# untitled.net
KiCad netlist of a schematic drawn in EAGLE
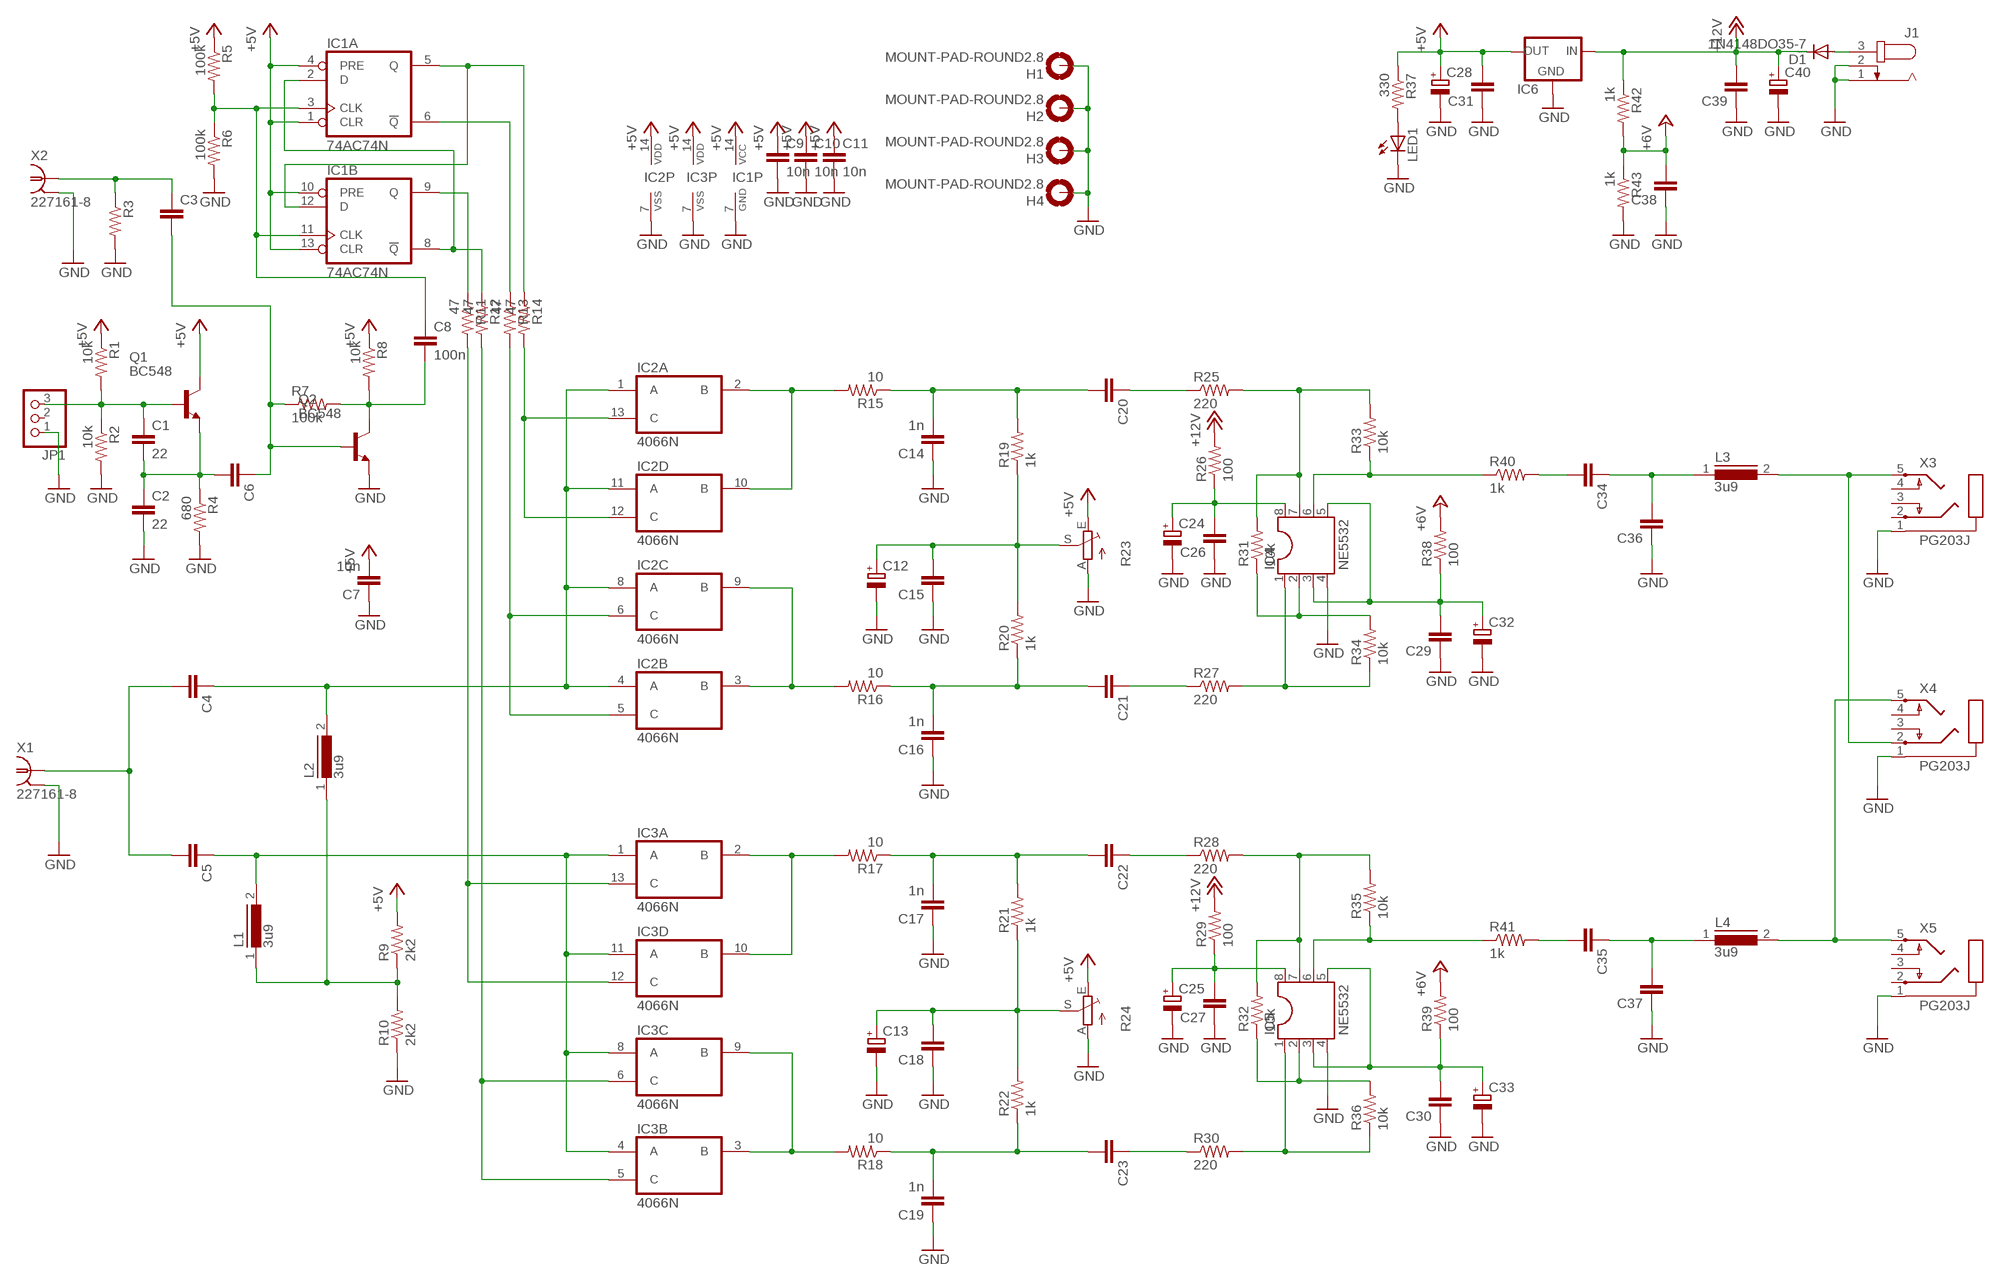
[diagram p0: schematic, sheet 1]

(export (version "E")
  (design (tool "Eeschema 10.0.6"))
  (components
    (comp (ref "C1")
      (value "22")
      (footprint "eagle-import:C025-025X050")
      (libsource (lib "eagle-import") (part "C-EU025-025X050"))
    )
    (comp (ref "C2")
      (value "22")
      (footprint "eagle-import:C025-025X050")
      (libsource (lib "eagle-import") (part "C-EU025-025X050"))
    )
    (comp (ref "C3")
      (value "C-EU050-025X075")
      (footprint "eagle-import:C050-025X075")
      (libsource (lib "eagle-import") (part "C-EU050-025X075"))
    )
    (comp (ref "C4")
      (value "C-EU050-025X075")
      (footprint "eagle-import:C050-025X075")
      (libsource (lib "eagle-import") (part "C-EU050-025X075"))
    )
    (comp (ref "C5")
      (value "C-EU050-025X075")
      (footprint "eagle-import:C050-025X075")
      (libsource (lib "eagle-import") (part "C-EU050-025X075"))
    )
    (comp (ref "C6")
      (value "C-EU050-025X075")
      (footprint "eagle-import:C050-025X075")
      (libsource (lib "eagle-import") (part "C-EU050-025X075"))
    )
    (comp (ref "C7")
      (value "10n")
      (footprint "eagle-import:C050-025X075")
      (libsource (lib "eagle-import") (part "C-EU050-025X075"))
    )
    (comp (ref "C8")
      (value "100n")
      (footprint "eagle-import:C075-032X103")
      (libsource (lib "eagle-import") (part "C-EU075-032X103"))
    )
    (comp (ref "C9")
      (value "10n")
      (footprint "eagle-import:C050-025X075")
      (libsource (lib "eagle-import") (part "C-EU050-025X075"))
    )
    (comp (ref "C10")
      (value "10n")
      (footprint "eagle-import:C050-025X075")
      (libsource (lib "eagle-import") (part "C-EU050-025X075"))
    )
    (comp (ref "C11")
      (value "10n")
      (footprint "eagle-import:C050-025X075")
      (libsource (lib "eagle-import") (part "C-EU050-025X075"))
    )
    (comp (ref "C12")
      (value "CPOL-EUE5-6")
      (footprint "eagle-import:E5-6")
      (libsource (lib "eagle-import") (part "CPOL-EUE5-6"))
    )
    (comp (ref "C13")
      (value "CPOL-EUE5-6")
      (footprint "eagle-import:E5-6")
      (libsource (lib "eagle-import") (part "CPOL-EUE5-6"))
    )
    (comp (ref "C14")
      (value "1n")
      (footprint "eagle-import:C050-025X075")
      (libsource (lib "eagle-import") (part "C-EU050-025X075"))
    )
    (comp (ref "C15")
      (value "C-EU050-025X075")
      (footprint "eagle-import:C050-025X075")
      (libsource (lib "eagle-import") (part "C-EU050-025X075"))
    )
    (comp (ref "C16")
      (value "1n")
      (footprint "eagle-import:C050-025X075")
      (libsource (lib "eagle-import") (part "C-EU050-025X075"))
    )
    (comp (ref "C17")
      (value "1n")
      (footprint "eagle-import:C050-025X075")
      (libsource (lib "eagle-import") (part "C-EU050-025X075"))
    )
    (comp (ref "C18")
      (value "C-EU050-025X075")
      (footprint "eagle-import:C050-025X075")
      (libsource (lib "eagle-import") (part "C-EU050-025X075"))
    )
    (comp (ref "C19")
      (value "1n")
      (footprint "eagle-import:C050-025X075")
      (libsource (lib "eagle-import") (part "C-EU050-025X075"))
    )
    (comp (ref "C20")
      (value "C-EU050-025X075")
      (footprint "eagle-import:C050-025X075")
      (libsource (lib "eagle-import") (part "C-EU050-025X075"))
    )
    (comp (ref "C21")
      (value "C-EU050-025X075")
      (footprint "eagle-import:C050-025X075")
      (libsource (lib "eagle-import") (part "C-EU050-025X075"))
    )
    (comp (ref "C22")
      (value "C-EU050-025X075")
      (footprint "eagle-import:C050-025X075")
      (libsource (lib "eagle-import") (part "C-EU050-025X075"))
    )
    (comp (ref "C23")
      (value "C-EU050-025X075")
      (footprint "eagle-import:C050-025X075")
      (libsource (lib "eagle-import") (part "C-EU050-025X075"))
    )
    (comp (ref "C24")
      (value "CPOL-EUE5-6")
      (footprint "eagle-import:E5-6")
      (libsource (lib "eagle-import") (part "CPOL-EUE5-6"))
    )
    (comp (ref "C25")
      (value "CPOL-EUE5-6")
      (footprint "eagle-import:E5-6")
      (libsource (lib "eagle-import") (part "CPOL-EUE5-6"))
    )
    (comp (ref "C26")
      (value "C-EU050-025X075")
      (footprint "eagle-import:C050-025X075")
      (libsource (lib "eagle-import") (part "C-EU050-025X075"))
    )
    (comp (ref "C27")
      (value "C-EU050-025X075")
      (footprint "eagle-import:C050-025X075")
      (libsource (lib "eagle-import") (part "C-EU050-025X075"))
    )
    (comp (ref "C28")
      (value "CPOL-EUE5-6")
      (footprint "eagle-import:E5-6")
      (libsource (lib "eagle-import") (part "CPOL-EUE5-6"))
    )
    (comp (ref "C29")
      (value "C-EU050-025X075")
      (footprint "eagle-import:C050-025X075")
      (libsource (lib "eagle-import") (part "C-EU050-025X075"))
    )
    (comp (ref "C30")
      (value "C-EU050-025X075")
      (footprint "eagle-import:C050-025X075")
      (libsource (lib "eagle-import") (part "C-EU050-025X075"))
    )
    (comp (ref "C31")
      (value "C-EU050-025X075")
      (footprint "eagle-import:C050-025X075")
      (libsource (lib "eagle-import") (part "C-EU050-025X075"))
    )
    (comp (ref "C32")
      (value "CPOL-EUE5-6")
      (footprint "eagle-import:E5-6")
      (libsource (lib "eagle-import") (part "CPOL-EUE5-6"))
    )
    (comp (ref "C33")
      (value "CPOL-EUE5-6")
      (footprint "eagle-import:E5-6")
      (libsource (lib "eagle-import") (part "CPOL-EUE5-6"))
    )
    (comp (ref "C34")
      (value "C-EU050-025X075")
      (footprint "eagle-import:C050-025X075")
      (libsource (lib "eagle-import") (part "C-EU050-025X075"))
    )
    (comp (ref "C35")
      (value "C-EU050-025X075")
      (footprint "eagle-import:C050-025X075")
      (libsource (lib "eagle-import") (part "C-EU050-025X075"))
    )
    (comp (ref "C36")
      (value "C-EU050-025X075")
      (footprint "eagle-import:C050-025X075")
      (libsource (lib "eagle-import") (part "C-EU050-025X075"))
    )
    (comp (ref "C37")
      (value "C-EU050-025X075")
      (footprint "eagle-import:C050-025X075")
      (libsource (lib "eagle-import") (part "C-EU050-025X075"))
    )
    (comp (ref "C38")
      (value "C-EU050-025X075")
      (footprint "eagle-import:C050-025X075")
      (libsource (lib "eagle-import") (part "C-EU050-025X075"))
    )
    (comp (ref "C39")
      (value "C-EU050-025X075")
      (footprint "eagle-import:C050-025X075")
      (libsource (lib "eagle-import") (part "C-EU050-025X075"))
    )
    (comp (ref "C40")
      (value "CPOL-EUE5-6")
      (footprint "eagle-import:E5-6")
      (libsource (lib "eagle-import") (part "CPOL-EUE5-6"))
    )
    (comp (ref "D1")
      (value "1N4148DO35-7")
      (footprint "eagle-import:DO35-7")
      (libsource (lib "eagle-import") (part "1N4148DO35-7"))
    )
    (comp (ref "H1")
      (value "MOUNT-PAD-ROUND2.8")
      (footprint "eagle-import:2,8-PAD")
      (libsource (lib "eagle-import") (part "MOUNT-PAD-ROUND2.8"))
    )
    (comp (ref "H2")
      (value "MOUNT-PAD-ROUND2.8")
      (footprint "eagle-import:2,8-PAD")
      (libsource (lib "eagle-import") (part "MOUNT-PAD-ROUND2.8"))
    )
    (comp (ref "H3")
      (value "MOUNT-PAD-ROUND2.8")
      (footprint "eagle-import:2,8-PAD")
      (libsource (lib "eagle-import") (part "MOUNT-PAD-ROUND2.8"))
    )
    (comp (ref "H4")
      (value "MOUNT-PAD-ROUND2.8")
      (footprint "eagle-import:2,8-PAD")
      (libsource (lib "eagle-import") (part "MOUNT-PAD-ROUND2.8"))
    )
    (comp (ref "IC1")
      (value "74AC74N")
      (footprint "eagle-import:DIL14")
      (libsource (lib "eagle-import") (part "7474NAC"))
    )
    (comp (ref "IC2")
      (value "4066N")
      (footprint "eagle-import:DIL14")
      (libsource (lib "eagle-import") (part "4066N"))
    )
    (comp (ref "IC3")
      (value "4066N")
      (footprint "eagle-import:DIL14")
      (libsource (lib "eagle-import") (part "4066N"))
    )
    (comp (ref "IC4")
      (value "NE5532")
      (footprint "eagle-import:DIL08")
      (libsource (lib "eagle-import") (part "DIL8"))
    )
    (comp (ref "IC5")
      (value "NE5532")
      (footprint "eagle-import:DIL08")
      (libsource (lib "eagle-import") (part "DIL8"))
    )
    (comp (ref "IC6")
      (value "78XXS")
      (footprint "eagle-import:78XXS")
      (libsource (lib "eagle-import") (part "78XXS"))
    )
    (comp (ref "J1")
      (value "JACK-PLUG0")
      (footprint "eagle-import:SPC4077")
      (libsource (lib "eagle-import") (part "JACK-PLUG0"))
    )
    (comp (ref "JP1")
      (value "PINHD-1X3")
      (footprint "eagle-import:1X03")
      (libsource (lib "eagle-import") (part "PINHD-1X3"))
    )
    (comp (ref "L1")
      (value "3u9")
      (footprint "eagle-import:MMICC7")
      (libsource (lib "eagle-import") (part "MMICC7"))
    )
    (comp (ref "L2")
      (value "3u9")
      (footprint "eagle-import:MMICC7")
      (libsource (lib "eagle-import") (part "MMICC7"))
    )
    (comp (ref "L3")
      (value "3u9")
      (footprint "eagle-import:MMICC7")
      (libsource (lib "eagle-import") (part "MMICC7"))
    )
    (comp (ref "L4")
      (value "3u9")
      (footprint "eagle-import:MMICC7")
      (libsource (lib "eagle-import") (part "MMICC7"))
    )
    (comp (ref "LED1")
      (value "LED3MM")
      (footprint "eagle-import:LED3MM")
      (libsource (lib "eagle-import") (part "LED3MM"))
    )
    (comp (ref "Q1")
      (value "BC548")
      (footprint "eagle-import:TO92-EBC")
      (libsource (lib "eagle-import") (part "BC548"))
    )
    (comp (ref "Q2")
      (value "BC548")
      (footprint "eagle-import:TO92-EBC")
      (libsource (lib "eagle-import") (part "BC548"))
    )
    (comp (ref "R1")
      (value "10k")
      (footprint "eagle-import:0207_7")
      (libsource (lib "eagle-import") (part "R-US_0207/7"))
    )
    (comp (ref "R2")
      (value "10k")
      (footprint "eagle-import:0207_7")
      (libsource (lib "eagle-import") (part "R-US_0207/7"))
    )
    (comp (ref "R3")
      (value "R-US_0207/7")
      (footprint "eagle-import:0207_7")
      (libsource (lib "eagle-import") (part "R-US_0207/7"))
    )
    (comp (ref "R4")
      (value "680")
      (footprint "eagle-import:0207_7")
      (libsource (lib "eagle-import") (part "R-US_0207/7"))
    )
    (comp (ref "R5")
      (value "100k")
      (footprint "eagle-import:0207_7")
      (libsource (lib "eagle-import") (part "R-US_0207/7"))
    )
    (comp (ref "R6")
      (value "100k")
      (footprint "eagle-import:0207_7")
      (libsource (lib "eagle-import") (part "R-US_0207/7"))
    )
    (comp (ref "R7")
      (value "100k")
      (footprint "eagle-import:0207_7")
      (libsource (lib "eagle-import") (part "R-US_0207/7"))
    )
    (comp (ref "R8")
      (value "10k")
      (footprint "eagle-import:0207_7")
      (libsource (lib "eagle-import") (part "R-US_0207/7"))
    )
    (comp (ref "R9")
      (value "2k2")
      (footprint "eagle-import:0207_7")
      (libsource (lib "eagle-import") (part "R-US_0207/7"))
    )
    (comp (ref "R10")
      (value "2k2")
      (footprint "eagle-import:0207_7")
      (libsource (lib "eagle-import") (part "R-US_0207/7"))
    )
    (comp (ref "R11")
      (value "47")
      (footprint "eagle-import:0207_7")
      (libsource (lib "eagle-import") (part "R-US_0207/7"))
    )
    (comp (ref "R12")
      (value "47")
      (footprint "eagle-import:0207_7")
      (libsource (lib "eagle-import") (part "R-US_0207/7"))
    )
    (comp (ref "R13")
      (value "47")
      (footprint "eagle-import:0207_7")
      (libsource (lib "eagle-import") (part "R-US_0207/7"))
    )
    (comp (ref "R14")
      (value "47")
      (footprint "eagle-import:0207_7")
      (libsource (lib "eagle-import") (part "R-US_0207/7"))
    )
    (comp (ref "R15")
      (value "10")
      (footprint "eagle-import:0207_7")
      (libsource (lib "eagle-import") (part "R-US_0207/7"))
    )
    (comp (ref "R16")
      (value "10")
      (footprint "eagle-import:0207_7")
      (libsource (lib "eagle-import") (part "R-US_0207/7"))
    )
    (comp (ref "R17")
      (value "10")
      (footprint "eagle-import:0207_7")
      (libsource (lib "eagle-import") (part "R-US_0207/7"))
    )
    (comp (ref "R18")
      (value "10")
      (footprint "eagle-import:0207_7")
      (libsource (lib "eagle-import") (part "R-US_0207/7"))
    )
    (comp (ref "R19")
      (value "1k")
      (footprint "eagle-import:0207_7")
      (libsource (lib "eagle-import") (part "R-US_0207/7"))
    )
    (comp (ref "R20")
      (value "1k")
      (footprint "eagle-import:0207_7")
      (libsource (lib "eagle-import") (part "R-US_0207/7"))
    )
    (comp (ref "R21")
      (value "1k")
      (footprint "eagle-import:0207_7")
      (libsource (lib "eagle-import") (part "R-US_0207/7"))
    )
    (comp (ref "R22")
      (value "1k")
      (footprint "eagle-import:0207_7")
      (libsource (lib "eagle-import") (part "R-US_0207/7"))
    )
    (comp (ref "R23")
      (value "TRIM_EU-B64Y")
      (footprint "eagle-import:B64Y")
      (libsource (lib "eagle-import") (part "TRIM_EU-B64Y"))
    )
    (comp (ref "R24")
      (value "TRIM_EU-B64Y")
      (footprint "eagle-import:B64Y")
      (libsource (lib "eagle-import") (part "TRIM_EU-B64Y"))
    )
    (comp (ref "R25")
      (value "220")
      (footprint "eagle-import:0207_7")
      (libsource (lib "eagle-import") (part "R-US_0207/7"))
    )
    (comp (ref "R26")
      (value "100")
      (footprint "eagle-import:0207_7")
      (libsource (lib "eagle-import") (part "R-US_0207/7"))
    )
    (comp (ref "R27")
      (value "220")
      (footprint "eagle-import:0207_7")
      (libsource (lib "eagle-import") (part "R-US_0207/7"))
    )
    (comp (ref "R28")
      (value "220")
      (footprint "eagle-import:0207_7")
      (libsource (lib "eagle-import") (part "R-US_0207/7"))
    )
    (comp (ref "R29")
      (value "100")
      (footprint "eagle-import:0207_7")
      (libsource (lib "eagle-import") (part "R-US_0207/7"))
    )
    (comp (ref "R30")
      (value "220")
      (footprint "eagle-import:0207_7")
      (libsource (lib "eagle-import") (part "R-US_0207/7"))
    )
    (comp (ref "R31")
      (value "10k")
      (footprint "eagle-import:0207_7")
      (libsource (lib "eagle-import") (part "R-US_0207/7"))
    )
    (comp (ref "R32")
      (value "10k")
      (footprint "eagle-import:0207_7")
      (libsource (lib "eagle-import") (part "R-US_0207/7"))
    )
    (comp (ref "R33")
      (value "10k")
      (footprint "eagle-import:0207_7")
      (libsource (lib "eagle-import") (part "R-US_0207/7"))
    )
    (comp (ref "R34")
      (value "10k")
      (footprint "eagle-import:0207_7")
      (libsource (lib "eagle-import") (part "R-US_0207/7"))
    )
    (comp (ref "R35")
      (value "10k")
      (footprint "eagle-import:0207_7")
      (libsource (lib "eagle-import") (part "R-US_0207/7"))
    )
    (comp (ref "R36")
      (value "10k")
      (footprint "eagle-import:0207_7")
      (libsource (lib "eagle-import") (part "R-US_0207/7"))
    )
    (comp (ref "R37")
      (value "330")
      (footprint "eagle-import:0207_7")
      (libsource (lib "eagle-import") (part "R-US_0207/7"))
    )
    (comp (ref "R38")
      (value "100")
      (footprint "eagle-import:0207_7")
      (libsource (lib "eagle-import") (part "R-US_0207/7"))
    )
    (comp (ref "R39")
      (value "100")
      (footprint "eagle-import:0207_7")
      (libsource (lib "eagle-import") (part "R-US_0207/7"))
    )
    (comp (ref "R40")
      (value "1k")
      (footprint "eagle-import:0207_7")
      (libsource (lib "eagle-import") (part "R-US_0207/7"))
    )
    (comp (ref "R41")
      (value "1k")
      (footprint "eagle-import:0207_7")
      (libsource (lib "eagle-import") (part "R-US_0207/7"))
    )
    (comp (ref "R42")
      (value "1k")
      (footprint "eagle-import:0207_7")
      (libsource (lib "eagle-import") (part "R-US_0207/7"))
    )
    (comp (ref "R43")
      (value "1k")
      (footprint "eagle-import:0207_7")
      (libsource (lib "eagle-import") (part "R-US_0207/7"))
    )
    (comp (ref "X1")
      (value "227161-8")
      (footprint "eagle-import:AMP_227161")
      (libsource (lib "eagle-import") (part "?227161-8"))
    )
    (comp (ref "X2")
      (value "227161-8")
      (footprint "eagle-import:AMP_227161")
      (libsource (lib "eagle-import") (part "?227161-8"))
    )
    (comp (ref "X3")
      (value "PG203J")
      (footprint "eagle-import:PG203J")
      (libsource (lib "eagle-import") (part "PG203J"))
    )
    (comp (ref "X4")
      (value "PG203J")
      (footprint "eagle-import:PG203J")
      (libsource (lib "eagle-import") (part "PG203J"))
    )
    (comp (ref "X5")
      (value "PG203J")
      (footprint "eagle-import:PG203J")
      (libsource (lib "eagle-import") (part "PG203J"))
    )
  )
  (nets
    (net (code "1") (name "+5V") (class "Default")
      (node (ref "C10") (pin "1") (pinfunction "1_1") (pintype "passive"))
      (node (ref "C11") (pin "1") (pinfunction "1_1") (pintype "passive"))
      (node (ref "C28") (pin "+") (pinfunction "+_+") (pintype "passive"))
      (node (ref "C31") (pin "2") (pinfunction "2_2") (pintype "passive"))
      (node (ref "C7") (pin "2") (pinfunction "2_2") (pintype "passive"))
      (node (ref "C9") (pin "1") (pinfunction "1_1") (pintype "passive"))
      (node (ref "IC1") (pin "1") (pinfunction "CLR_1") (pintype "input"))
      (node (ref "IC1") (pin "10") (pinfunction "PRE_10") (pintype "input"))
      (node (ref "IC1") (pin "13") (pinfunction "CLR_13") (pintype "input"))
      (node (ref "IC1") (pin "14") (pinfunction "VCC_14") (pintype "power_in"))
      (node (ref "IC1") (pin "4") (pinfunction "PRE_4") (pintype "input"))
      (node (ref "IC2") (pin "14") (pinfunction "VDD_14") (pintype "power_in"))
      (node (ref "IC3") (pin "14") (pinfunction "VDD_14") (pintype "power_in"))
      (node (ref "IC6") (pin "OUT") (pinfunction "OUT_OUT") (pintype "passive"))
      (node (ref "Q1") (pin "C") (pinfunction "C_C") (pintype "passive"))
      (node (ref "R1") (pin "1") (pinfunction "1_1") (pintype "passive"))
      (node (ref "R23") (pin "E") (pinfunction "E_E") (pintype "passive"))
      (node (ref "R24") (pin "E") (pinfunction "E_E") (pintype "passive"))
      (node (ref "R37") (pin "1") (pinfunction "1_1") (pintype "passive"))
      (node (ref "R5") (pin "1") (pinfunction "1_1") (pintype "passive"))
      (node (ref "R8") (pin "1") (pinfunction "1_1") (pintype "passive"))
      (node (ref "R9") (pin "2") (pinfunction "2_2") (pintype "passive"))
    )
    (net (code "2") (name "+6V") (class "Default")
      (node (ref "C38") (pin "2") (pinfunction "2_2") (pintype "passive"))
      (node (ref "R38") (pin "2") (pinfunction "2_2") (pintype "passive"))
      (node (ref "R39") (pin "2") (pinfunction "2_2") (pintype "passive"))
      (node (ref "R42") (pin "2") (pinfunction "2_2") (pintype "passive"))
      (node (ref "R43") (pin "1") (pinfunction "1_1") (pintype "passive"))
    )
    (net (code "3") (name "+12V") (class "Default")
      (node (ref "C39") (pin "2") (pinfunction "2_2") (pintype "passive"))
      (node (ref "C40") (pin "+") (pinfunction "+_+") (pintype "passive"))
      (node (ref "D1") (pin "C") (pinfunction "C_C") (pintype "passive"))
      (node (ref "IC6") (pin "IN") (pinfunction "IN_IN") (pintype "input"))
      (node (ref "R26") (pin "2") (pinfunction "2_2") (pintype "passive"))
      (node (ref "R29") (pin "2") (pinfunction "2_2") (pintype "passive"))
      (node (ref "R42") (pin "1") (pinfunction "1_1") (pintype "passive"))
    )
    (net (code "4") (name "GND") (class "Default")
      (node (ref "C10") (pin "2") (pinfunction "2_2") (pintype "passive"))
      (node (ref "C11") (pin "2") (pinfunction "2_2") (pintype "passive"))
      (node (ref "C12") (pin "-") (pinfunction "-_-") (pintype "passive"))
      (node (ref "C13") (pin "-") (pinfunction "-_-") (pintype "passive"))
      (node (ref "C14") (pin "1") (pinfunction "1_1") (pintype "passive"))
      (node (ref "C15") (pin "1") (pinfunction "1_1") (pintype "passive"))
      (node (ref "C16") (pin "1") (pinfunction "1_1") (pintype "passive"))
      (node (ref "C17") (pin "1") (pinfunction "1_1") (pintype "passive"))
      (node (ref "C18") (pin "1") (pinfunction "1_1") (pintype "passive"))
      (node (ref "C19") (pin "1") (pinfunction "1_1") (pintype "passive"))
      (node (ref "C2") (pin "2") (pinfunction "2_2") (pintype "passive"))
      (node (ref "C24") (pin "-") (pinfunction "-_-") (pintype "passive"))
      (node (ref "C25") (pin "-") (pinfunction "-_-") (pintype "passive"))
      (node (ref "C26") (pin "1") (pinfunction "1_1") (pintype "passive"))
      (node (ref "C27") (pin "1") (pinfunction "1_1") (pintype "passive"))
      (node (ref "C28") (pin "-") (pinfunction "-_-") (pintype "passive"))
      (node (ref "C29") (pin "1") (pinfunction "1_1") (pintype "passive"))
      (node (ref "C30") (pin "1") (pinfunction "1_1") (pintype "passive"))
      (node (ref "C31") (pin "1") (pinfunction "1_1") (pintype "passive"))
      (node (ref "C32") (pin "-") (pinfunction "-_-") (pintype "passive"))
      (node (ref "C33") (pin "-") (pinfunction "-_-") (pintype "passive"))
      (node (ref "C36") (pin "1") (pinfunction "1_1") (pintype "passive"))
      (node (ref "C37") (pin "1") (pinfunction "1_1") (pintype "passive"))
      (node (ref "C38") (pin "1") (pinfunction "1_1") (pintype "passive"))
      (node (ref "C39") (pin "1") (pinfunction "1_1") (pintype "passive"))
      (node (ref "C40") (pin "-") (pinfunction "-_-") (pintype "passive"))
      (node (ref "C7") (pin "1") (pinfunction "1_1") (pintype "passive"))
      (node (ref "C9") (pin "2") (pinfunction "2_2") (pintype "passive"))
      (node (ref "H1") (pin "B2,8") (pinfunction "MOUNT_B2,8") (pintype "passive"))
      (node (ref "H2") (pin "B2,8") (pinfunction "MOUNT_B2,8") (pintype "passive"))
      (node (ref "H3") (pin "B2,8") (pinfunction "MOUNT_B2,8") (pintype "passive"))
      (node (ref "H4") (pin "B2,8") (pinfunction "MOUNT_B2,8") (pintype "passive"))
      (node (ref "IC1") (pin "7") (pinfunction "GND_7") (pintype "power_in"))
      (node (ref "IC2") (pin "7") (pinfunction "VSS_7") (pintype "power_in"))
      (node (ref "IC3") (pin "7") (pinfunction "VSS_7") (pintype "power_in"))
      (node (ref "IC4") (pin "4") (pinfunction "4_4") (pintype "passive"))
      (node (ref "IC5") (pin "4") (pinfunction "4_4") (pintype "passive"))
      (node (ref "IC6") (pin "GND") (pinfunction "GND_GND") (pintype "input"))
      (node (ref "J1") (pin "1") (pinfunction "1_1") (pintype "passive"))
      (node (ref "J1") (pin "2") (pinfunction "2_2") (pintype "passive"))
      (node (ref "JP1") (pin "1") (pinfunction "1_1") (pintype "passive"))
      (node (ref "LED1") (pin "K") (pinfunction "C_K") (pintype "passive"))
      (node (ref "Q2") (pin "E") (pinfunction "E_E") (pintype "passive"))
      (node (ref "R10") (pin "1") (pinfunction "1_1") (pintype "passive"))
      (node (ref "R2") (pin "2") (pinfunction "2_2") (pintype "passive"))
      (node (ref "R23") (pin "A") (pinfunction "A_A") (pintype "passive"))
      (node (ref "R24") (pin "A") (pinfunction "A_A") (pintype "passive"))
      (node (ref "R3") (pin "2") (pinfunction "2_2") (pintype "passive"))
      (node (ref "R4") (pin "2") (pinfunction "2_2") (pintype "passive"))
      (node (ref "R43") (pin "2") (pinfunction "2_2") (pintype "passive"))
      (node (ref "R6") (pin "2") (pinfunction "2_2") (pintype "passive"))
      (node (ref "X1") (pin "2") (pinfunction "2_2") (pintype "passive"))
      (node (ref "X2") (pin "2") (pinfunction "2_2") (pintype "passive"))
      (node (ref "X3") (pin "1") (pinfunction "1_1") (pintype "passive"))
      (node (ref "X4") (pin "1") (pinfunction "1_1") (pintype "passive"))
      (node (ref "X5") (pin "1") (pinfunction "1_1") (pintype "passive"))
    )
    (net (code "5") (name "Net-(C1-Pad1)") (class "Default")
      (node (ref "C1") (pin "1") (pinfunction "1_1") (pintype "passive"))
      (node (ref "JP1") (pin "3") (pinfunction "3_3") (pintype "passive"))
      (node (ref "Q1") (pin "B") (pinfunction "B_B") (pintype "passive"))
      (node (ref "R1") (pin "2") (pinfunction "2_2") (pintype "passive"))
      (node (ref "R2") (pin "1") (pinfunction "1_1") (pintype "passive"))
    )
    (net (code "6") (name "Net-(C1-Pad2)") (class "Default")
      (node (ref "C1") (pin "2") (pinfunction "2_2") (pintype "passive"))
      (node (ref "C2") (pin "1") (pinfunction "1_1") (pintype "passive"))
      (node (ref "C6") (pin "2") (pinfunction "2_2") (pintype "passive"))
      (node (ref "Q1") (pin "E") (pinfunction "E_E") (pintype "passive"))
      (node (ref "R4") (pin "1") (pinfunction "1_1") (pintype "passive"))
    )
    (net (code "7") (name "Net-(C3-Pad1)") (class "Default")
      (node (ref "C3") (pin "1") (pinfunction "1_1") (pintype "passive"))
      (node (ref "R3") (pin "1") (pinfunction "1_1") (pintype "passive"))
      (node (ref "X2") (pin "1") (pinfunction "1_1") (pintype "passive"))
    )
    (net (code "8") (name "Net-(C3-Pad2)") (class "Default")
      (node (ref "C3") (pin "2") (pinfunction "2_2") (pintype "passive"))
      (node (ref "C6") (pin "1") (pinfunction "1_1") (pintype "passive"))
      (node (ref "Q2") (pin "B") (pinfunction "B_B") (pintype "passive"))
      (node (ref "R7") (pin "1") (pinfunction "1_1") (pintype "passive"))
    )
    (net (code "9") (name "Net-(C4-Pad2)") (class "Default")
      (node (ref "C4") (pin "2") (pinfunction "2_2") (pintype "passive"))
      (node (ref "C5") (pin "2") (pinfunction "2_2") (pintype "passive"))
      (node (ref "X1") (pin "1") (pinfunction "1_1") (pintype "passive"))
    )
    (net (code "10") (name "Net-(C8-Pad2)") (class "Default")
      (node (ref "C8") (pin "2") (pinfunction "2_2") (pintype "passive"))
      (node (ref "Q2") (pin "C") (pinfunction "C_C") (pintype "passive"))
      (node (ref "R7") (pin "2") (pinfunction "2_2") (pintype "passive"))
      (node (ref "R8") (pin "2") (pinfunction "2_2") (pintype "passive"))
    )
    (net (code "11") (name "Net-(C12-Pad+)") (class "Default")
      (node (ref "C12") (pin "+") (pinfunction "+_+") (pintype "passive"))
      (node (ref "C15") (pin "2") (pinfunction "2_2") (pintype "passive"))
      (node (ref "R19") (pin "1") (pinfunction "1_1") (pintype "passive"))
      (node (ref "R20") (pin "2") (pinfunction "2_2") (pintype "passive"))
      (node (ref "R23") (pin "S") (pinfunction "S_S") (pintype "passive"))
    )
    (net (code "12") (name "Net-(C13-Pad+)") (class "Default")
      (node (ref "C13") (pin "+") (pinfunction "+_+") (pintype "passive"))
      (node (ref "C18") (pin "2") (pinfunction "2_2") (pintype "passive"))
      (node (ref "R21") (pin "1") (pinfunction "1_1") (pintype "passive"))
      (node (ref "R22") (pin "2") (pinfunction "2_2") (pintype "passive"))
      (node (ref "R24") (pin "S") (pinfunction "S_S") (pintype "passive"))
    )
    (net (code "13") (name "Net-(C14-Pad2)") (class "Default")
      (node (ref "C14") (pin "2") (pinfunction "2_2") (pintype "passive"))
      (node (ref "C20") (pin "2") (pinfunction "2_2") (pintype "passive"))
      (node (ref "R15") (pin "1") (pinfunction "1_1") (pintype "passive"))
      (node (ref "R19") (pin "2") (pinfunction "2_2") (pintype "passive"))
    )
    (net (code "14") (name "Net-(C16-Pad2)") (class "Default")
      (node (ref "C16") (pin "2") (pinfunction "2_2") (pintype "passive"))
      (node (ref "C21") (pin "2") (pinfunction "2_2") (pintype "passive"))
      (node (ref "R16") (pin "1") (pinfunction "1_1") (pintype "passive"))
      (node (ref "R20") (pin "1") (pinfunction "1_1") (pintype "passive"))
    )
    (net (code "15") (name "Net-(C17-Pad2)") (class "Default")
      (node (ref "C17") (pin "2") (pinfunction "2_2") (pintype "passive"))
      (node (ref "C22") (pin "2") (pinfunction "2_2") (pintype "passive"))
      (node (ref "R17") (pin "1") (pinfunction "1_1") (pintype "passive"))
      (node (ref "R21") (pin "2") (pinfunction "2_2") (pintype "passive"))
    )
    (net (code "16") (name "Net-(C19-Pad2)") (class "Default")
      (node (ref "C19") (pin "2") (pinfunction "2_2") (pintype "passive"))
      (node (ref "C23") (pin "2") (pinfunction "2_2") (pintype "passive"))
      (node (ref "R18") (pin "1") (pinfunction "1_1") (pintype "passive"))
      (node (ref "R22") (pin "1") (pinfunction "1_1") (pintype "passive"))
    )
    (net (code "17") (name "Net-(C20-Pad1)") (class "Default")
      (node (ref "C20") (pin "1") (pinfunction "1_1") (pintype "passive"))
      (node (ref "R25") (pin "1") (pinfunction "1_1") (pintype "passive"))
    )
    (net (code "18") (name "Net-(C21-Pad1)") (class "Default")
      (node (ref "C21") (pin "1") (pinfunction "1_1") (pintype "passive"))
      (node (ref "R27") (pin "1") (pinfunction "1_1") (pintype "passive"))
    )
    (net (code "19") (name "Net-(C22-Pad1)") (class "Default")
      (node (ref "C22") (pin "1") (pinfunction "1_1") (pintype "passive"))
      (node (ref "R28") (pin "1") (pinfunction "1_1") (pintype "passive"))
    )
    (net (code "20") (name "Net-(C23-Pad1)") (class "Default")
      (node (ref "C23") (pin "1") (pinfunction "1_1") (pintype "passive"))
      (node (ref "R30") (pin "1") (pinfunction "1_1") (pintype "passive"))
    )
    (net (code "21") (name "Net-(C24-Pad+)") (class "Default")
      (node (ref "C24") (pin "+") (pinfunction "+_+") (pintype "passive"))
      (node (ref "C26") (pin "2") (pinfunction "2_2") (pintype "passive"))
      (node (ref "IC4") (pin "8") (pinfunction "8_8") (pintype "passive"))
      (node (ref "R26") (pin "1") (pinfunction "1_1") (pintype "passive"))
    )
    (net (code "22") (name "Net-(C25-Pad+)") (class "Default")
      (node (ref "C25") (pin "+") (pinfunction "+_+") (pintype "passive"))
      (node (ref "C27") (pin "2") (pinfunction "2_2") (pintype "passive"))
      (node (ref "IC5") (pin "8") (pinfunction "8_8") (pintype "passive"))
      (node (ref "R29") (pin "1") (pinfunction "1_1") (pintype "passive"))
    )
    (net (code "23") (name "Net-(C29-Pad2)") (class "Default")
      (node (ref "C29") (pin "2") (pinfunction "2_2") (pintype "passive"))
      (node (ref "C32") (pin "+") (pinfunction "+_+") (pintype "passive"))
      (node (ref "IC4") (pin "3") (pinfunction "3_3") (pintype "passive"))
      (node (ref "IC4") (pin "5") (pinfunction "5_5") (pintype "passive"))
      (node (ref "R38") (pin "1") (pinfunction "1_1") (pintype "passive"))
    )
    (net (code "24") (name "Net-(C30-Pad2)") (class "Default")
      (node (ref "C30") (pin "2") (pinfunction "2_2") (pintype "passive"))
      (node (ref "C33") (pin "+") (pinfunction "+_+") (pintype "passive"))
      (node (ref "IC5") (pin "3") (pinfunction "3_3") (pintype "passive"))
      (node (ref "IC5") (pin "5") (pinfunction "5_5") (pintype "passive"))
      (node (ref "R39") (pin "1") (pinfunction "1_1") (pintype "passive"))
    )
    (net (code "25") (name "Net-(C34-Pad1)") (class "Default")
      (node (ref "C34") (pin "1") (pinfunction "1_1") (pintype "passive"))
      (node (ref "C36") (pin "2") (pinfunction "2_2") (pintype "passive"))
      (node (ref "L3") (pin "1") (pinfunction "1_1") (pintype "passive"))
    )
    (net (code "26") (name "Net-(C34-Pad2)") (class "Default")
      (node (ref "C34") (pin "2") (pinfunction "2_2") (pintype "passive"))
      (node (ref "R40") (pin "2") (pinfunction "2_2") (pintype "passive"))
    )
    (net (code "27") (name "Net-(C35-Pad1)") (class "Default")
      (node (ref "C35") (pin "1") (pinfunction "1_1") (pintype "passive"))
      (node (ref "C37") (pin "2") (pinfunction "2_2") (pintype "passive"))
      (node (ref "L4") (pin "1") (pinfunction "1_1") (pintype "passive"))
    )
    (net (code "28") (name "Net-(C35-Pad2)") (class "Default")
      (node (ref "C35") (pin "2") (pinfunction "2_2") (pintype "passive"))
      (node (ref "R41") (pin "2") (pinfunction "2_2") (pintype "passive"))
    )
    (net (code "29") (name "Net-(D1-PadA)") (class "Default")
      (node (ref "D1") (pin "A") (pinfunction "A_A") (pintype "passive"))
      (node (ref "J1") (pin "3") (pinfunction "3_3") (pintype "passive"))
    )
    (net (code "30") (name "Net-(IC1A-CLK)") (class "Default")
      (node (ref "C8") (pin "1") (pinfunction "1_1") (pintype "passive"))
      (node (ref "IC1") (pin "11") (pinfunction "CLK_11") (pintype "input"))
      (node (ref "IC1") (pin "3") (pinfunction "CLK_3") (pintype "input"))
      (node (ref "R5") (pin "2") (pinfunction "2_2") (pintype "passive"))
      (node (ref "R6") (pin "1") (pinfunction "1_1") (pintype "passive"))
    )
    (net (code "31") (name "Net-(IC1A-D)") (class "Default")
      (node (ref "IC1") (pin "2") (pinfunction "D_2") (pintype "input"))
      (node (ref "IC1") (pin "8") (pinfunction "~{Q}_8") (pintype "output"))
      (node (ref "R12") (pin "1") (pinfunction "1_1") (pintype "passive"))
    )
    (net (code "32") (name "Net-(IC1A-Q)") (class "Default")
      (node (ref "IC1") (pin "12") (pinfunction "D_12") (pintype "input"))
      (node (ref "IC1") (pin "5") (pinfunction "Q_5") (pintype "output"))
      (node (ref "R14") (pin "1") (pinfunction "1_1") (pintype "passive"))
    )
    (net (code "33") (name "Net-(IC1A-~{Q})") (class "Default")
      (node (ref "IC1") (pin "6") (pinfunction "~{Q}_6") (pintype "output"))
      (node (ref "R13") (pin "1") (pinfunction "1_1") (pintype "passive"))
    )
    (net (code "34") (name "Net-(IC1B-Q)") (class "Default")
      (node (ref "IC1") (pin "9") (pinfunction "Q_9") (pintype "output"))
      (node (ref "R11") (pin "1") (pinfunction "1_1") (pintype "passive"))
    )
    (net (code "35") (name "Net-(IC2A-A)") (class "Default")
      (node (ref "C4") (pin "1") (pinfunction "1_1") (pintype "passive"))
      (node (ref "IC2") (pin "1") (pinfunction "A_1") (pintype "tri_state"))
      (node (ref "IC2") (pin "11") (pinfunction "A_11") (pintype "tri_state"))
      (node (ref "IC2") (pin "4") (pinfunction "A_4") (pintype "tri_state"))
      (node (ref "IC2") (pin "8") (pinfunction "A_8") (pintype "tri_state"))
      (node (ref "L2") (pin "2") (pinfunction "2_2") (pintype "passive"))
    )
    (net (code "36") (name "Net-(IC2A-B)") (class "Default")
      (node (ref "IC2") (pin "10") (pinfunction "B_10") (pintype "tri_state"))
      (node (ref "IC2") (pin "2") (pinfunction "B_2") (pintype "tri_state"))
      (node (ref "R15") (pin "2") (pinfunction "2_2") (pintype "passive"))
    )
    (net (code "37") (name "Net-(IC2A-C)") (class "Default")
      (node (ref "IC2") (pin "12") (pinfunction "C_12") (pintype "input"))
      (node (ref "IC2") (pin "13") (pinfunction "C_13") (pintype "input"))
      (node (ref "R14") (pin "2") (pinfunction "2_2") (pintype "passive"))
    )
    (net (code "38") (name "Net-(IC2B-B)") (class "Default")
      (node (ref "IC2") (pin "3") (pinfunction "B_3") (pintype "tri_state"))
      (node (ref "IC2") (pin "9") (pinfunction "B_9") (pintype "tri_state"))
      (node (ref "R16") (pin "2") (pinfunction "2_2") (pintype "passive"))
    )
    (net (code "39") (name "Net-(IC2B-C)") (class "Default")
      (node (ref "IC2") (pin "5") (pinfunction "C_5") (pintype "input"))
      (node (ref "IC2") (pin "6") (pinfunction "C_6") (pintype "input"))
      (node (ref "R13") (pin "2") (pinfunction "2_2") (pintype "passive"))
    )
    (net (code "40") (name "Net-(IC3A-A)") (class "Default")
      (node (ref "C5") (pin "1") (pinfunction "1_1") (pintype "passive"))
      (node (ref "IC3") (pin "1") (pinfunction "A_1") (pintype "tri_state"))
      (node (ref "IC3") (pin "11") (pinfunction "A_11") (pintype "tri_state"))
      (node (ref "IC3") (pin "4") (pinfunction "A_4") (pintype "tri_state"))
      (node (ref "IC3") (pin "8") (pinfunction "A_8") (pintype "tri_state"))
      (node (ref "L1") (pin "2") (pinfunction "2_2") (pintype "passive"))
    )
    (net (code "41") (name "Net-(IC3A-B)") (class "Default")
      (node (ref "IC3") (pin "10") (pinfunction "B_10") (pintype "tri_state"))
      (node (ref "IC3") (pin "2") (pinfunction "B_2") (pintype "tri_state"))
      (node (ref "R17") (pin "2") (pinfunction "2_2") (pintype "passive"))
    )
    (net (code "42") (name "Net-(IC3A-C)") (class "Default")
      (node (ref "IC3") (pin "12") (pinfunction "C_12") (pintype "input"))
      (node (ref "IC3") (pin "13") (pinfunction "C_13") (pintype "input"))
      (node (ref "R11") (pin "2") (pinfunction "2_2") (pintype "passive"))
    )
    (net (code "43") (name "Net-(IC3B-B)") (class "Default")
      (node (ref "IC3") (pin "3") (pinfunction "B_3") (pintype "tri_state"))
      (node (ref "IC3") (pin "9") (pinfunction "B_9") (pintype "tri_state"))
      (node (ref "R18") (pin "2") (pinfunction "2_2") (pintype "passive"))
    )
    (net (code "44") (name "Net-(IC3B-C)") (class "Default")
      (node (ref "IC3") (pin "5") (pinfunction "C_5") (pintype "input"))
      (node (ref "IC3") (pin "6") (pinfunction "C_6") (pintype "input"))
      (node (ref "R12") (pin "2") (pinfunction "2_2") (pintype "passive"))
    )
    (net (code "45") (name "Net-(IC4-Pad1)") (class "Default")
      (node (ref "IC4") (pin "1") (pinfunction "1_1") (pintype "passive"))
      (node (ref "R27") (pin "2") (pinfunction "2_2") (pintype "passive"))
      (node (ref "R34") (pin "1") (pinfunction "1_1") (pintype "passive"))
    )
    (net (code "46") (name "Net-(IC4-Pad2)") (class "Default")
      (node (ref "IC4") (pin "2") (pinfunction "2_2") (pintype "passive"))
      (node (ref "R31") (pin "1") (pinfunction "1_1") (pintype "passive"))
      (node (ref "R34") (pin "2") (pinfunction "2_2") (pintype "passive"))
    )
    (net (code "47") (name "Net-(IC4-Pad6)") (class "Default")
      (node (ref "IC4") (pin "6") (pinfunction "6_6") (pintype "passive"))
      (node (ref "R33") (pin "1") (pinfunction "1_1") (pintype "passive"))
      (node (ref "R40") (pin "1") (pinfunction "1_1") (pintype "passive"))
    )
    (net (code "48") (name "Net-(IC4-Pad7)") (class "Default")
      (node (ref "IC4") (pin "7") (pinfunction "7_7") (pintype "passive"))
      (node (ref "R25") (pin "2") (pinfunction "2_2") (pintype "passive"))
      (node (ref "R31") (pin "2") (pinfunction "2_2") (pintype "passive"))
      (node (ref "R33") (pin "2") (pinfunction "2_2") (pintype "passive"))
    )
    (net (code "49") (name "Net-(IC5-Pad1)") (class "Default")
      (node (ref "IC5") (pin "1") (pinfunction "1_1") (pintype "passive"))
      (node (ref "R30") (pin "2") (pinfunction "2_2") (pintype "passive"))
      (node (ref "R36") (pin "1") (pinfunction "1_1") (pintype "passive"))
    )
    (net (code "50") (name "Net-(IC5-Pad2)") (class "Default")
      (node (ref "IC5") (pin "2") (pinfunction "2_2") (pintype "passive"))
      (node (ref "R32") (pin "1") (pinfunction "1_1") (pintype "passive"))
      (node (ref "R36") (pin "2") (pinfunction "2_2") (pintype "passive"))
    )
    (net (code "51") (name "Net-(IC5-Pad6)") (class "Default")
      (node (ref "IC5") (pin "6") (pinfunction "6_6") (pintype "passive"))
      (node (ref "R35") (pin "1") (pinfunction "1_1") (pintype "passive"))
      (node (ref "R41") (pin "1") (pinfunction "1_1") (pintype "passive"))
    )
    (net (code "52") (name "Net-(IC5-Pad7)") (class "Default")
      (node (ref "IC5") (pin "7") (pinfunction "7_7") (pintype "passive"))
      (node (ref "R28") (pin "2") (pinfunction "2_2") (pintype "passive"))
      (node (ref "R32") (pin "2") (pinfunction "2_2") (pintype "passive"))
      (node (ref "R35") (pin "2") (pinfunction "2_2") (pintype "passive"))
    )
    (net (code "53") (name "Net-(L1-Pad1)") (class "Default")
      (node (ref "L1") (pin "1") (pinfunction "1_1") (pintype "passive"))
      (node (ref "L2") (pin "1") (pinfunction "1_1") (pintype "passive"))
      (node (ref "R10") (pin "2") (pinfunction "2_2") (pintype "passive"))
      (node (ref "R9") (pin "1") (pinfunction "1_1") (pintype "passive"))
    )
    (net (code "54") (name "Net-(L3-Pad2)") (class "Default")
      (node (ref "L3") (pin "2") (pinfunction "2_2") (pintype "passive"))
      (node (ref "X3") (pin "5") (pinfunction "5_5") (pintype "passive"))
      (node (ref "X4") (pin "2") (pinfunction "2_2") (pintype "passive"))
    )
    (net (code "55") (name "Net-(L4-Pad2)") (class "Default")
      (node (ref "L4") (pin "2") (pinfunction "2_2") (pintype "passive"))
      (node (ref "X4") (pin "5") (pinfunction "5_5") (pintype "passive"))
      (node (ref "X5") (pin "5") (pinfunction "5_5") (pintype "passive"))
    )
    (net (code "56") (name "Net-(LED1-PadA)") (class "Default")
      (node (ref "LED1") (pin "A") (pinfunction "A_A") (pintype "passive"))
      (node (ref "R37") (pin "2") (pinfunction "2_2") (pintype "passive"))
    )
    (net (code "57") (name "unconnected-(JP1-Pad2)") (class "Default")
      (node (ref "JP1") (pin "2") (pinfunction "2_2") (pintype "passive"))
    )
    (net (code "58") (name "unconnected-(X3-Pad2)") (class "Default")
      (node (ref "X3") (pin "2") (pinfunction "2_2") (pintype "passive"))
    )
    (net (code "59") (name "unconnected-(X3-Pad3)") (class "Default")
      (node (ref "X3") (pin "3") (pinfunction "3_3") (pintype "passive"))
    )
    (net (code "60") (name "unconnected-(X3-Pad4)") (class "Default")
      (node (ref "X3") (pin "4") (pinfunction "4_4") (pintype "passive"))
    )
    (net (code "61") (name "unconnected-(X4-Pad3)") (class "Default")
      (node (ref "X4") (pin "3") (pinfunction "3_3") (pintype "passive"))
    )
    (net (code "62") (name "unconnected-(X4-Pad4)") (class "Default")
      (node (ref "X4") (pin "4") (pinfunction "4_4") (pintype "passive"))
    )
    (net (code "63") (name "unconnected-(X5-Pad2)") (class "Default")
      (node (ref "X5") (pin "2") (pinfunction "2_2") (pintype "passive"))
    )
    (net (code "64") (name "unconnected-(X5-Pad3)") (class "Default")
      (node (ref "X5") (pin "3") (pinfunction "3_3") (pintype "passive"))
    )
    (net (code "65") (name "unconnected-(X5-Pad4)") (class "Default")
      (node (ref "X5") (pin "4") (pinfunction "4_4") (pintype "passive"))
    )
  )
)
